# DAC.net
KiCad netlist of a schematic drawn in Altium Designer
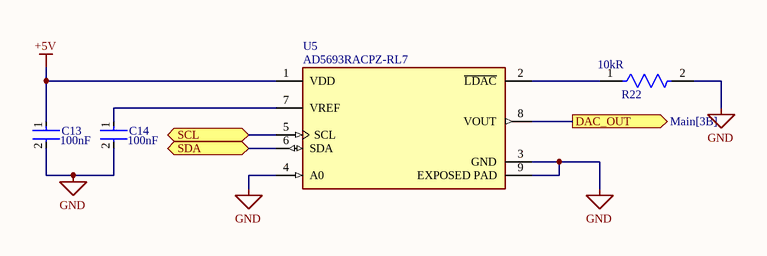
[diagram p0: DAC.SchDoc]

(export (version "E")
  (design (tool "Eeschema 10.0.6"))
  (components
    (comp (ref "C13")
      (value "C2012X7T2E104K125AE")
      (footprint "FP-C2012-125-0_45-MFG")
      (description "CAP CER 0.1UF 250V X7T 0805")
      (fields (field (name "CAPACITANCE") "100nF") (field (name "TOLERANCE") "10%"))
      (libsource (lib "Altium Content Vault") (part "b4654b650e69147ec39a6b967a45e02"))
    )
    (comp (ref "C14")
      (value "C2012X7T2E104K125AE")
      (footprint "FP-C2012-125-0_45-MFG")
      (description "CAP CER 0.1UF 250V X7T 0805")
      (fields (field (name "CAPACITANCE") "100nF") (field (name "TOLERANCE") "10%"))
      (libsource (lib "Altium Content Vault") (part "b4654b650e69147ec39a6b967a45e02"))
    )
    (comp (ref "R22")
      (value "ERJ-P06F1002V")
      (footprint "FP-ERJP06-MFG")
      (description "RES SMD 10K OHM 1% 1/2W 0805")
      (fields (field (name "TOLERANCE") "1%") (field (name "RESISTANCE") "10kR"))
      (libsource (lib "Altium Content Vault") (part "1029c3af85768c4190bb7ad29bc67b5"))
    )
    (comp (ref "U5")
      (value "AD5693RACPZ-RL7")
      (footprint "FP-CP-8-10-IPC_C")
      (description "IC DAC 16BIT V-OUT 8LFCSP")
      (libsource (lib "Altium Content Vault") (part "62576e0a5eb7ccdfbfe8c0f25c5ee64"))
    )
  )
  (nets
    (net (code "1") (name "+5V") (class "Default")
      (node (ref "C13") (pin "1") (pinfunction "1_1") (pintype "passive"))
      (node (ref "U5") (pin "1") (pinfunction "VDD_1") (pintype "power_in"))
    )
    (net (code "2") (name "/DAC_OUT") (class "Default")
      (node (ref "U5") (pin "8") (pinfunction "VOUT_8") (pintype "output"))
    )
    (net (code "3") (name "/SCL") (class "Default")
      (node (ref "U5") (pin "5") (pinfunction "SCL_5") (pintype "input"))
    )
    (net (code "4") (name "/SDA") (class "Default")
      (node (ref "U5") (pin "6") (pinfunction "SDA_6") (pintype "bidirectional"))
    )
    (net (code "5") (name "GND") (class "Default")
      (node (ref "C13") (pin "2") (pinfunction "2_2") (pintype "passive"))
      (node (ref "C14") (pin "2") (pinfunction "2_2") (pintype "passive"))
      (node (ref "R22") (pin "2") (pinfunction "2_2") (pintype "passive"))
      (node (ref "U5") (pin "3") (pinfunction "GND_3") (pintype "power_in"))
      (node (ref "U5") (pin "4") (pinfunction "A0_4") (pintype "input"))
      (node (ref "U5") (pin "9") (pinfunction "EXPOSED_PAD_9") (pintype "power_in"))
    )
    (net (code "6") (name "Net-(U5-VREF)") (class "Default")
      (node (ref "C14") (pin "1") (pinfunction "1_1") (pintype "passive"))
      (node (ref "U5") (pin "7") (pinfunction "VREF_7") (pintype "power_in"))
    )
    (net (code "7") (name "Net-(U5-~{LDAC})") (class "Default")
      (node (ref "R22") (pin "1") (pinfunction "1_1") (pintype "passive"))
      (node (ref "U5") (pin "2") (pinfunction "~{LDAC}_2") (pintype "passive"))
    )
  )
)
